# main.net
KiCad netlist of a schematic drawn in EAGLE
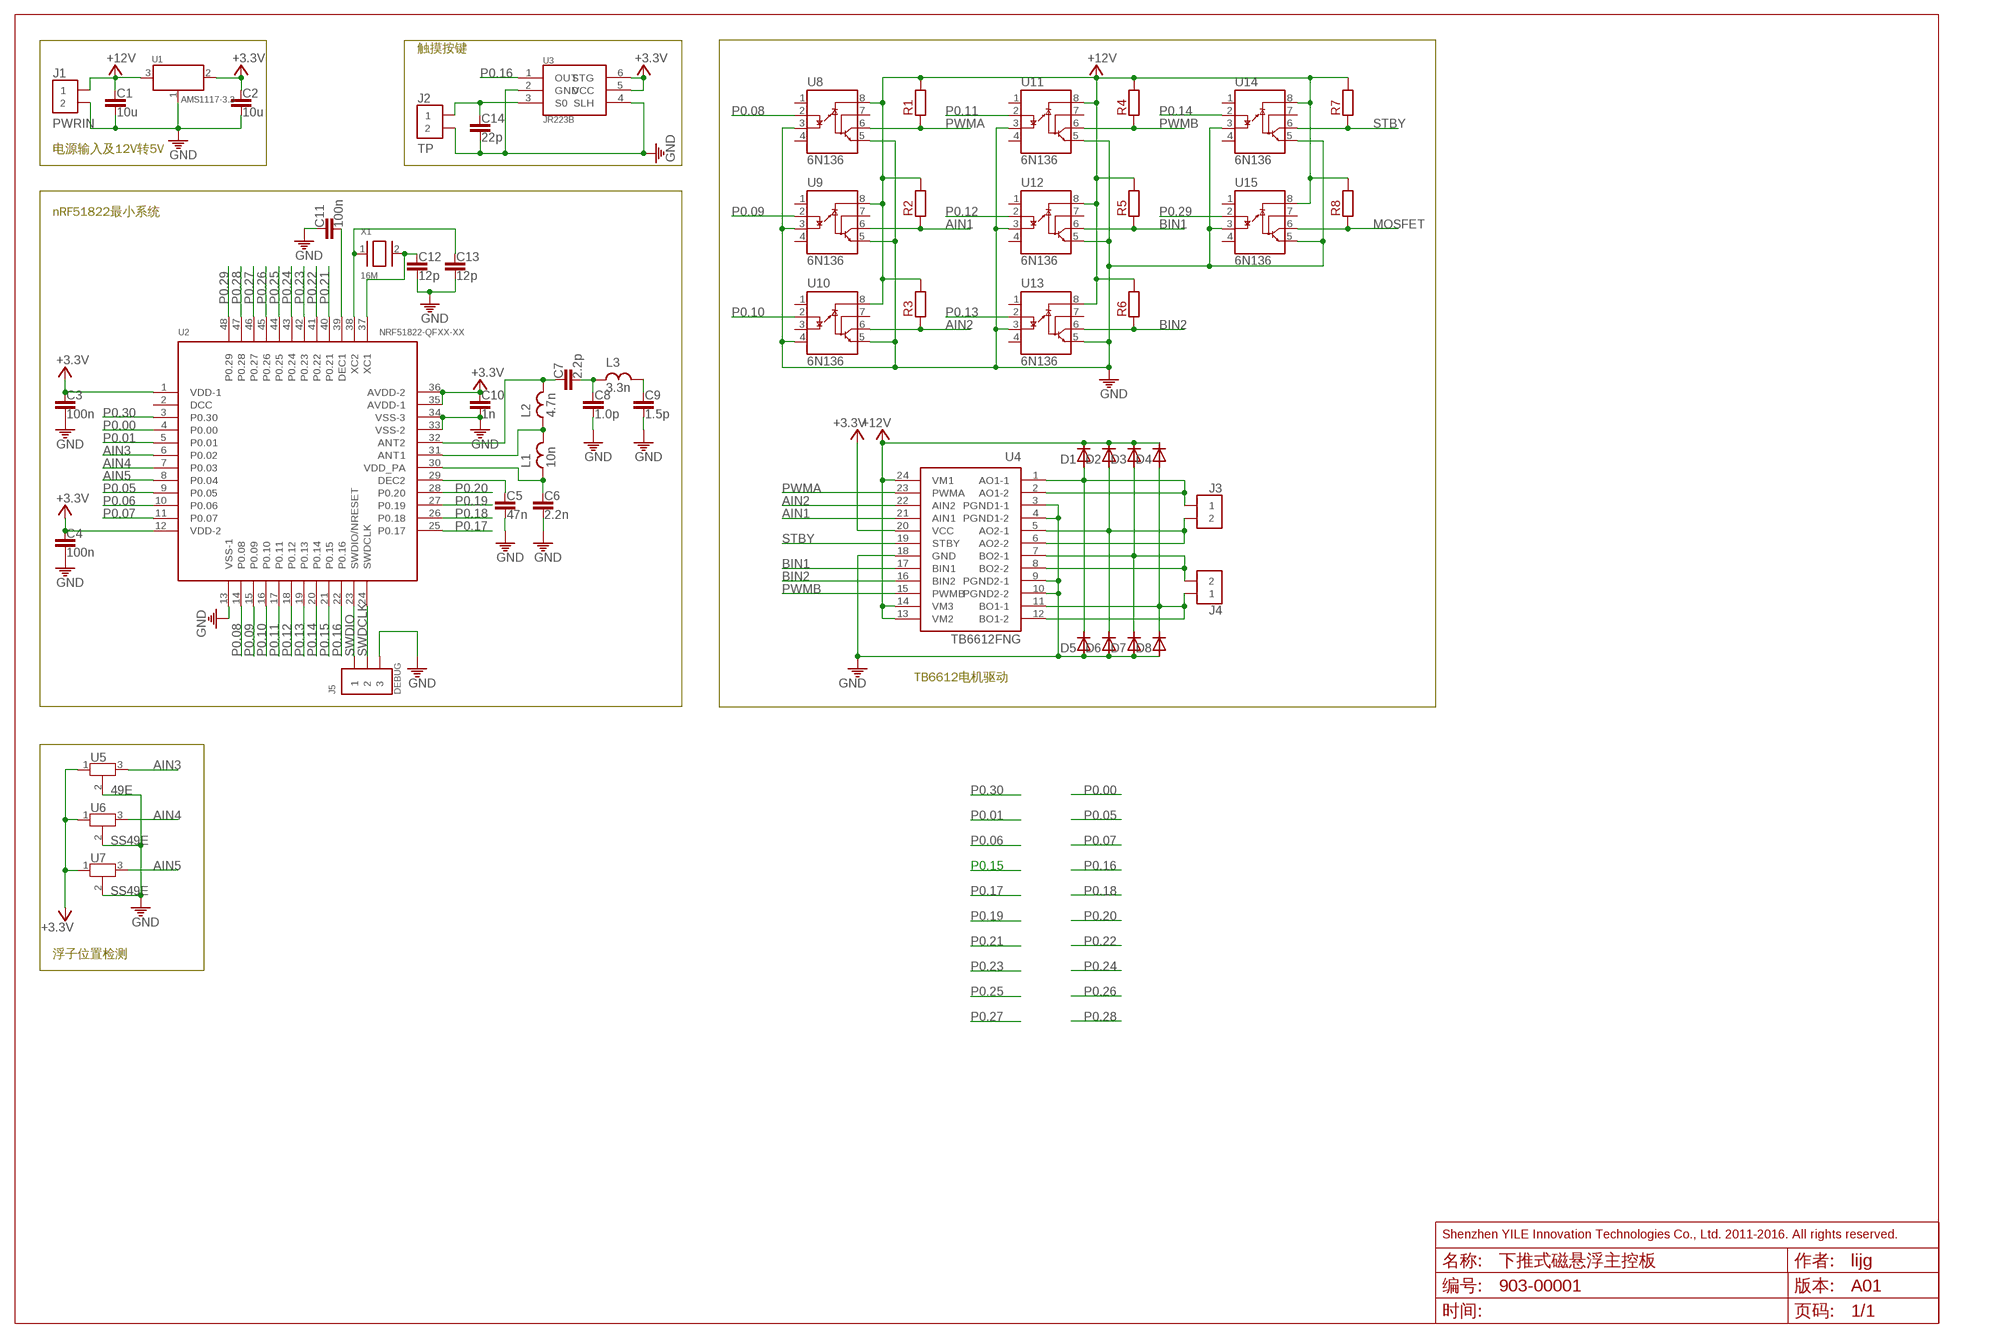
[diagram p0: schematic, sheet 1]

(export (version "E")
  (design (tool "Eeschema 10.0.6"))
  (components
    (comp (ref "C1")
      (value "10u")
      (footprint "eagle-import:0805")
      (libsource (lib "eagle-import") (part "C0805"))
    )
    (comp (ref "C2")
      (value "10u")
      (footprint "eagle-import:0805")
      (libsource (lib "eagle-import") (part "C0805"))
    )
    (comp (ref "C3")
      (value "100n")
      (footprint "eagle-import:0805")
      (libsource (lib "eagle-import") (part "C0805"))
    )
    (comp (ref "C4")
      (value "100n")
      (footprint "eagle-import:0805")
      (libsource (lib "eagle-import") (part "C0805"))
    )
    (comp (ref "C5")
      (value "47n")
      (footprint "eagle-import:0805")
      (libsource (lib "eagle-import") (part "C0805"))
    )
    (comp (ref "C6")
      (value "2.2n")
      (footprint "eagle-import:0805")
      (libsource (lib "eagle-import") (part "C0805"))
    )
    (comp (ref "C7")
      (value "2.2p")
      (footprint "eagle-import:0805")
      (libsource (lib "eagle-import") (part "C0805"))
    )
    (comp (ref "C8")
      (value "1.0p")
      (footprint "eagle-import:0805")
      (libsource (lib "eagle-import") (part "C0805"))
    )
    (comp (ref "C9")
      (value "1.5p")
      (footprint "eagle-import:0805")
      (libsource (lib "eagle-import") (part "C0805"))
    )
    (comp (ref "C10")
      (value "1n")
      (footprint "eagle-import:0805")
      (libsource (lib "eagle-import") (part "C0805"))
    )
    (comp (ref "C11")
      (value "100n")
      (footprint "eagle-import:0805")
      (libsource (lib "eagle-import") (part "C0805"))
    )
    (comp (ref "C12")
      (value "12p")
      (footprint "eagle-import:0805")
      (libsource (lib "eagle-import") (part "C0805"))
    )
    (comp (ref "C13")
      (value "12p")
      (footprint "eagle-import:0805")
      (libsource (lib "eagle-import") (part "C0805"))
    )
    (comp (ref "C14")
      (value "22p")
      (footprint "eagle-import:0805")
      (libsource (lib "eagle-import") (part "C0805"))
    )
    (comp (ref "D1")
      (value "D0805")
      (footprint "eagle-import:0805")
      (libsource (lib "eagle-import") (part "D0805"))
    )
    (comp (ref "D2")
      (value "D0805")
      (footprint "eagle-import:0805")
      (libsource (lib "eagle-import") (part "D0805"))
    )
    (comp (ref "D3")
      (value "D0805")
      (footprint "eagle-import:0805")
      (libsource (lib "eagle-import") (part "D0805"))
    )
    (comp (ref "D4")
      (value "D0805")
      (footprint "eagle-import:0805")
      (libsource (lib "eagle-import") (part "D0805"))
    )
    (comp (ref "D5")
      (value "D0805")
      (footprint "eagle-import:0805")
      (libsource (lib "eagle-import") (part "D0805"))
    )
    (comp (ref "D6")
      (value "D0805")
      (footprint "eagle-import:0805")
      (libsource (lib "eagle-import") (part "D0805"))
    )
    (comp (ref "D7")
      (value "D0805")
      (footprint "eagle-import:0805")
      (libsource (lib "eagle-import") (part "D0805"))
    )
    (comp (ref "D8")
      (value "D0805")
      (footprint "eagle-import:0805")
      (libsource (lib "eagle-import") (part "D0805"))
    )
    (comp (ref "J1")
      (value "PWRIN")
      (footprint "eagle-import:SIP2-100")
      (libsource (lib "eagle-import") (part "CON2X12X1-DIP2-100"))
    )
    (comp (ref "J2")
      (value "TP")
      (footprint "eagle-import:SIP2-100")
      (libsource (lib "eagle-import") (part "CON2X12X1-DIP2-100"))
    )
    (comp (ref "J3")
      (value "CON2X12X1-DIP2-100")
      (footprint "eagle-import:SIP2-100")
      (libsource (lib "eagle-import") (part "CON2X12X1-DIP2-100"))
    )
    (comp (ref "J4")
      (value "CON2X12X1-DIP2-100")
      (footprint "eagle-import:SIP2-100")
      (libsource (lib "eagle-import") (part "CON2X12X1-DIP2-100"))
    )
    (comp (ref "J5")
      (value "DEBUG")
      (footprint "eagle-import:SIP3-100")
      (libsource (lib "eagle-import") (part "CON3X1"))
    )
    (comp (ref "L1")
      (value "10n")
      (footprint "eagle-import:0805")
      (libsource (lib "eagle-import") (part "L0805"))
    )
    (comp (ref "L2")
      (value "4.7n")
      (footprint "eagle-import:0805")
      (libsource (lib "eagle-import") (part "L0805"))
    )
    (comp (ref "L3")
      (value "3.3n")
      (footprint "eagle-import:0805")
      (libsource (lib "eagle-import") (part "L0805"))
    )
    (comp (ref "R1")
      (value "R0805")
      (footprint "eagle-import:0805")
      (libsource (lib "eagle-import") (part "R0805"))
    )
    (comp (ref "R2")
      (value "R0805")
      (footprint "eagle-import:0805")
      (libsource (lib "eagle-import") (part "R0805"))
    )
    (comp (ref "R3")
      (value "R0805")
      (footprint "eagle-import:0805")
      (libsource (lib "eagle-import") (part "R0805"))
    )
    (comp (ref "R4")
      (value "R0805")
      (footprint "eagle-import:0805")
      (libsource (lib "eagle-import") (part "R0805"))
    )
    (comp (ref "R5")
      (value "R0805")
      (footprint "eagle-import:0805")
      (libsource (lib "eagle-import") (part "R0805"))
    )
    (comp (ref "R6")
      (value "R0805")
      (footprint "eagle-import:0805")
      (libsource (lib "eagle-import") (part "R0805"))
    )
    (comp (ref "R7")
      (value "R0805")
      (footprint "eagle-import:0805")
      (libsource (lib "eagle-import") (part "R0805"))
    )
    (comp (ref "R8")
      (value "R0805")
      (footprint "eagle-import:0805")
      (libsource (lib "eagle-import") (part "R0805"))
    )
    (comp (ref "U1")
      (value "AMS1117-3.3")
      (footprint "eagle-import:SOT-223")
      (libsource (lib "eagle-import") (part "AMS1117"))
    )
    (comp (ref "U2")
      (value "NRF51822-QFXX-XX")
      (footprint "eagle-import:QFN48-6.0A-0.4A")
      (libsource (lib "eagle-import") (part "NRF51822-QFXX-XX"))
    )
    (comp (ref "U3")
      (value "JR223B")
      (footprint "eagle-import:SSOP6-P-118-0.6A")
      (libsource (lib "eagle-import") (part "JR223B"))
    )
    (comp (ref "U4")
      (value "TB6612FNG")
      (footprint "eagle-import:SSOP24-P-300-0.65A")
      (libsource (lib "eagle-import") (part "TB6612FNG"))
    )
    (comp (ref "U5")
      (value "49E")
      (footprint "eagle-import:AH3503")
      (libsource (lib "eagle-import") (part "AH3503"))
    )
    (comp (ref "U6")
      (value "SS49E")
      (footprint "eagle-import:AH3503")
      (libsource (lib "eagle-import") (part "AH3503"))
    )
    (comp (ref "U7")
      (value "SS49E")
      (footprint "eagle-import:AH3503")
      (libsource (lib "eagle-import") (part "AH3503"))
    )
    (comp (ref "U8")
      (value "6N136")
      (footprint "eagle-import:SOP8-900A-2.54A")
      (libsource (lib "eagle-import") (part "6N136"))
    )
    (comp (ref "U9")
      (value "6N136")
      (footprint "eagle-import:SOP8-900A-2.54A")
      (libsource (lib "eagle-import") (part "6N136"))
    )
    (comp (ref "U10")
      (value "6N136")
      (footprint "eagle-import:SOP8-900A-2.54A")
      (libsource (lib "eagle-import") (part "6N136"))
    )
    (comp (ref "U11")
      (value "6N136")
      (footprint "eagle-import:SOP8-900A-2.54A")
      (libsource (lib "eagle-import") (part "6N136"))
    )
    (comp (ref "U12")
      (value "6N136")
      (footprint "eagle-import:SOP8-900A-2.54A")
      (libsource (lib "eagle-import") (part "6N136"))
    )
    (comp (ref "U13")
      (value "6N136")
      (footprint "eagle-import:SOP8-900A-2.54A")
      (libsource (lib "eagle-import") (part "6N136"))
    )
    (comp (ref "U14")
      (value "6N136")
      (footprint "eagle-import:SOP8-900A-2.54A")
      (libsource (lib "eagle-import") (part "6N136"))
    )
    (comp (ref "U15")
      (value "6N136")
      (footprint "eagle-import:SOP8-900A-2.54A")
      (libsource (lib "eagle-import") (part "6N136"))
    )
    (comp (ref "X1")
      (value "16M")
      (footprint "eagle-import:S5032B")
      (libsource (lib "eagle-import") (part "S5032B"))
    )
  )
  (nets
    (net (code "1") (name "+3.3V") (class "Default")
      (node (ref "C10") (pin "1") (pinfunction "1_1") (pintype "bidirectional"))
      (node (ref "C2") (pin "1") (pinfunction "1_1") (pintype "bidirectional"))
      (node (ref "C3") (pin "1") (pinfunction "1_1") (pintype "bidirectional"))
      (node (ref "C4") (pin "1") (pinfunction "1_1") (pintype "bidirectional"))
      (node (ref "U1") (pin "2") (pinfunction "VOUT_2") (pintype "bidirectional"))
      (node (ref "U2") (pin "1") (pinfunction "VDD-1_1") (pintype "bidirectional"))
      (node (ref "U2") (pin "12") (pinfunction "VDD-2_12") (pintype "bidirectional"))
      (node (ref "U2") (pin "35") (pinfunction "AVDD-1_35") (pintype "bidirectional"))
      (node (ref "U2") (pin "36") (pinfunction "AVDD-2_36") (pintype "bidirectional"))
      (node (ref "U3") (pin "5") (pinfunction "VCC_5") (pintype "bidirectional"))
      (node (ref "U3") (pin "6") (pinfunction "STG_6") (pintype "bidirectional"))
      (node (ref "U4") (pin "20") (pinfunction "VCC_20") (pintype "bidirectional"))
      (node (ref "U5") (pin "1") (pinfunction "P$1_1") (pintype "bidirectional"))
      (node (ref "U6") (pin "1") (pinfunction "P$1_1") (pintype "bidirectional"))
      (node (ref "U7") (pin "1") (pinfunction "P$1_1") (pintype "bidirectional"))
    )
    (net (code "2") (name "+12V") (class "Default")
      (node (ref "C1") (pin "1") (pinfunction "1_1") (pintype "bidirectional"))
      (node (ref "D1") (pin "2") (pinfunction "P$2_2") (pintype "bidirectional"))
      (node (ref "D2") (pin "2") (pinfunction "P$2_2") (pintype "bidirectional"))
      (node (ref "D3") (pin "2") (pinfunction "P$2_2") (pintype "bidirectional"))
      (node (ref "D4") (pin "2") (pinfunction "P$2_2") (pintype "bidirectional"))
      (node (ref "J1") (pin "P$1") (pinfunction "1_P$1") (pintype "bidirectional"))
      (node (ref "R1") (pin "2") (pinfunction "2_2") (pintype "bidirectional"))
      (node (ref "R2") (pin "2") (pinfunction "2_2") (pintype "bidirectional"))
      (node (ref "R3") (pin "2") (pinfunction "2_2") (pintype "bidirectional"))
      (node (ref "R4") (pin "2") (pinfunction "2_2") (pintype "bidirectional"))
      (node (ref "R5") (pin "2") (pinfunction "2_2") (pintype "bidirectional"))
      (node (ref "R6") (pin "2") (pinfunction "2_2") (pintype "bidirectional"))
      (node (ref "R7") (pin "2") (pinfunction "2_2") (pintype "bidirectional"))
      (node (ref "R8") (pin "2") (pinfunction "2_2") (pintype "bidirectional"))
      (node (ref "U1") (pin "3") (pinfunction "VIN_3") (pintype "bidirectional"))
      (node (ref "U10") (pin "8") (pinfunction "VCC_8") (pintype "bidirectional"))
      (node (ref "U11") (pin "8") (pinfunction "VCC_8") (pintype "bidirectional"))
      (node (ref "U12") (pin "8") (pinfunction "VCC_8") (pintype "bidirectional"))
      (node (ref "U13") (pin "8") (pinfunction "VCC_8") (pintype "bidirectional"))
      (node (ref "U14") (pin "8") (pinfunction "VCC_8") (pintype "bidirectional"))
      (node (ref "U15") (pin "8") (pinfunction "VCC_8") (pintype "bidirectional"))
      (node (ref "U4") (pin "13") (pinfunction "VM2_13") (pintype "bidirectional"))
      (node (ref "U4") (pin "14") (pinfunction "VM3_14") (pintype "bidirectional"))
      (node (ref "U4") (pin "24") (pinfunction "VM1_24") (pintype "bidirectional"))
      (node (ref "U8") (pin "8") (pinfunction "VCC_8") (pintype "bidirectional"))
      (node (ref "U9") (pin "8") (pinfunction "VCC_8") (pintype "bidirectional"))
    )
    (net (code "3") (name "/AIN1") (class "Default")
      (node (ref "R2") (pin "1") (pinfunction "1_1") (pintype "bidirectional"))
      (node (ref "U4") (pin "21") (pinfunction "AIN1_21") (pintype "bidirectional"))
      (node (ref "U9") (pin "6") (pinfunction "VO_6") (pintype "bidirectional"))
    )
    (net (code "4") (name "/AIN2") (class "Default")
      (node (ref "R3") (pin "1") (pinfunction "1_1") (pintype "bidirectional"))
      (node (ref "U10") (pin "6") (pinfunction "VO_6") (pintype "bidirectional"))
      (node (ref "U4") (pin "22") (pinfunction "AIN2_22") (pintype "bidirectional"))
    )
    (net (code "5") (name "/AIN3") (class "Default")
      (node (ref "U2") (pin "6") (pinfunction "P0.02_6") (pintype "bidirectional"))
      (node (ref "U5") (pin "3") (pinfunction "P$3_3") (pintype "bidirectional"))
    )
    (net (code "6") (name "/AIN4") (class "Default")
      (node (ref "U2") (pin "7") (pinfunction "P0.03_7") (pintype "bidirectional"))
      (node (ref "U6") (pin "3") (pinfunction "P$3_3") (pintype "bidirectional"))
    )
    (net (code "7") (name "/AIN5") (class "Default")
      (node (ref "U2") (pin "8") (pinfunction "P0.04_8") (pintype "bidirectional"))
      (node (ref "U7") (pin "3") (pinfunction "P$3_3") (pintype "bidirectional"))
    )
    (net (code "8") (name "/BIN1") (class "Default")
      (node (ref "R5") (pin "1") (pinfunction "1_1") (pintype "bidirectional"))
      (node (ref "U12") (pin "6") (pinfunction "VO_6") (pintype "bidirectional"))
      (node (ref "U4") (pin "17") (pinfunction "BIN1_17") (pintype "bidirectional"))
    )
    (net (code "9") (name "/BIN2") (class "Default")
      (node (ref "R6") (pin "1") (pinfunction "1_1") (pintype "bidirectional"))
      (node (ref "U13") (pin "6") (pinfunction "VO_6") (pintype "bidirectional"))
      (node (ref "U4") (pin "16") (pinfunction "BIN2_16") (pintype "bidirectional"))
    )
    (net (code "10") (name "/MOSFET") (class "Default")
      (node (ref "R8") (pin "1") (pinfunction "1_1") (pintype "bidirectional"))
      (node (ref "U15") (pin "6") (pinfunction "VO_6") (pintype "bidirectional"))
    )
    (net (code "11") (name "/P0.00") (class "Default")
      (node (ref "U2") (pin "4") (pinfunction "P0.00_4") (pintype "bidirectional"))
    )
    (net (code "12") (name "/P0.01") (class "Default")
      (node (ref "U2") (pin "5") (pinfunction "P0.01_5") (pintype "bidirectional"))
    )
    (net (code "13") (name "/P0.05") (class "Default")
      (node (ref "U2") (pin "9") (pinfunction "P0.05_9") (pintype "bidirectional"))
    )
    (net (code "14") (name "/P0.06") (class "Default")
      (node (ref "U2") (pin "10") (pinfunction "P0.06_10") (pintype "bidirectional"))
    )
    (net (code "15") (name "/P0.07") (class "Default")
      (node (ref "U2") (pin "11") (pinfunction "P0.07_11") (pintype "bidirectional"))
    )
    (net (code "16") (name "/P0.08") (class "Default")
      (node (ref "U2") (pin "14") (pinfunction "P0.08_14") (pintype "bidirectional"))
      (node (ref "U8") (pin "2") (pinfunction "A_2") (pintype "bidirectional"))
    )
    (net (code "17") (name "/P0.09") (class "Default")
      (node (ref "U2") (pin "15") (pinfunction "P0.09_15") (pintype "bidirectional"))
      (node (ref "U9") (pin "2") (pinfunction "A_2") (pintype "bidirectional"))
    )
    (net (code "18") (name "/P0.10") (class "Default")
      (node (ref "U10") (pin "2") (pinfunction "A_2") (pintype "bidirectional"))
      (node (ref "U2") (pin "16") (pinfunction "P0.10_16") (pintype "bidirectional"))
    )
    (net (code "19") (name "/P0.11") (class "Default")
      (node (ref "U11") (pin "2") (pinfunction "A_2") (pintype "bidirectional"))
      (node (ref "U2") (pin "17") (pinfunction "P0.11_17") (pintype "bidirectional"))
    )
    (net (code "20") (name "/P0.12") (class "Default")
      (node (ref "U12") (pin "2") (pinfunction "A_2") (pintype "bidirectional"))
      (node (ref "U2") (pin "18") (pinfunction "P0.12_18") (pintype "bidirectional"))
    )
    (net (code "21") (name "/P0.13") (class "Default")
      (node (ref "U13") (pin "2") (pinfunction "A_2") (pintype "bidirectional"))
      (node (ref "U2") (pin "19") (pinfunction "P0.13_19") (pintype "bidirectional"))
    )
    (net (code "22") (name "/P0.14") (class "Default")
      (node (ref "U14") (pin "2") (pinfunction "A_2") (pintype "bidirectional"))
      (node (ref "U2") (pin "20") (pinfunction "P0.14_20") (pintype "bidirectional"))
    )
    (net (code "23") (name "/P0.15") (class "Default")
      (node (ref "U2") (pin "21") (pinfunction "P0.15_21") (pintype "bidirectional"))
    )
    (net (code "24") (name "/P0.16") (class "Default")
      (node (ref "U2") (pin "22") (pinfunction "P0.16_22") (pintype "bidirectional"))
      (node (ref "U3") (pin "1") (pinfunction "OUT_1") (pintype "bidirectional"))
    )
    (net (code "25") (name "/P0.17") (class "Default")
      (node (ref "U2") (pin "25") (pinfunction "P0.17_25") (pintype "bidirectional"))
    )
    (net (code "26") (name "/P0.18") (class "Default")
      (node (ref "U2") (pin "26") (pinfunction "P0.18_26") (pintype "bidirectional"))
    )
    (net (code "27") (name "/P0.19") (class "Default")
      (node (ref "U2") (pin "27") (pinfunction "P0.19_27") (pintype "bidirectional"))
    )
    (net (code "28") (name "/P0.20") (class "Default")
      (node (ref "U2") (pin "28") (pinfunction "P0.20_28") (pintype "bidirectional"))
    )
    (net (code "29") (name "/P0.21") (class "Default")
      (node (ref "U2") (pin "40") (pinfunction "P0.21_40") (pintype "bidirectional"))
    )
    (net (code "30") (name "/P0.22") (class "Default")
      (node (ref "U2") (pin "41") (pinfunction "P0.22_41") (pintype "bidirectional"))
    )
    (net (code "31") (name "/P0.23") (class "Default")
      (node (ref "U2") (pin "42") (pinfunction "P0.23_42") (pintype "bidirectional"))
    )
    (net (code "32") (name "/P0.24") (class "Default")
      (node (ref "U2") (pin "43") (pinfunction "P0.24_43") (pintype "bidirectional"))
    )
    (net (code "33") (name "/P0.25") (class "Default")
      (node (ref "U2") (pin "44") (pinfunction "P0.25_44") (pintype "bidirectional"))
    )
    (net (code "34") (name "/P0.26") (class "Default")
      (node (ref "U2") (pin "45") (pinfunction "P0.26_45") (pintype "bidirectional"))
    )
    (net (code "35") (name "/P0.27") (class "Default")
      (node (ref "U2") (pin "46") (pinfunction "P0.27_46") (pintype "bidirectional"))
    )
    (net (code "36") (name "/P0.28") (class "Default")
      (node (ref "U2") (pin "47") (pinfunction "P0.28_47") (pintype "bidirectional"))
    )
    (net (code "37") (name "/P0.29") (class "Default")
      (node (ref "U15") (pin "2") (pinfunction "A_2") (pintype "bidirectional"))
      (node (ref "U2") (pin "48") (pinfunction "P0.29_48") (pintype "bidirectional"))
    )
    (net (code "38") (name "/P0.30") (class "Default")
      (node (ref "U2") (pin "3") (pinfunction "P0.30_3") (pintype "bidirectional"))
    )
    (net (code "39") (name "/PWMA") (class "Default")
      (node (ref "R1") (pin "1") (pinfunction "1_1") (pintype "bidirectional"))
      (node (ref "U4") (pin "23") (pinfunction "PWMA_23") (pintype "bidirectional"))
      (node (ref "U8") (pin "6") (pinfunction "VO_6") (pintype "bidirectional"))
    )
    (net (code "40") (name "/PWMB") (class "Default")
      (node (ref "R4") (pin "1") (pinfunction "1_1") (pintype "bidirectional"))
      (node (ref "U11") (pin "6") (pinfunction "VO_6") (pintype "bidirectional"))
      (node (ref "U4") (pin "15") (pinfunction "PWMB_15") (pintype "bidirectional"))
    )
    (net (code "41") (name "/STBY") (class "Default")
      (node (ref "R7") (pin "1") (pinfunction "1_1") (pintype "bidirectional"))
      (node (ref "U14") (pin "6") (pinfunction "VO_6") (pintype "bidirectional"))
      (node (ref "U4") (pin "19") (pinfunction "STBY_19") (pintype "bidirectional"))
    )
    (net (code "42") (name "/SWDCLK") (class "Default")
      (node (ref "J5") (pin "P$2") (pinfunction "2_P$2") (pintype "bidirectional"))
      (node (ref "U2") (pin "24") (pinfunction "SWDCLK_24") (pintype "bidirectional"))
    )
    (net (code "43") (name "/SWDIO") (class "Default")
      (node (ref "J5") (pin "P$1") (pinfunction "1_P$1") (pintype "bidirectional"))
      (node (ref "U2") (pin "23") (pinfunction "SWDIO/NRESET_23") (pintype "bidirectional"))
    )
    (net (code "44") (name "GND") (class "Default")
      (node (ref "C1") (pin "2") (pinfunction "2_2") (pintype "bidirectional"))
      (node (ref "C10") (pin "2") (pinfunction "2_2") (pintype "bidirectional"))
      (node (ref "C11") (pin "1") (pinfunction "1_1") (pintype "bidirectional"))
      (node (ref "C12") (pin "2") (pinfunction "2_2") (pintype "bidirectional"))
      (node (ref "C13") (pin "2") (pinfunction "2_2") (pintype "bidirectional"))
      (node (ref "C14") (pin "2") (pinfunction "2_2") (pintype "bidirectional"))
      (node (ref "C2") (pin "2") (pinfunction "2_2") (pintype "bidirectional"))
      (node (ref "C3") (pin "2") (pinfunction "2_2") (pintype "bidirectional"))
      (node (ref "C4") (pin "2") (pinfunction "2_2") (pintype "bidirectional"))
      (node (ref "C5") (pin "2") (pinfunction "2_2") (pintype "bidirectional"))
      (node (ref "C6") (pin "2") (pinfunction "2_2") (pintype "bidirectional"))
      (node (ref "C8") (pin "2") (pinfunction "2_2") (pintype "bidirectional"))
      (node (ref "C9") (pin "2") (pinfunction "2_2") (pintype "bidirectional"))
      (node (ref "D5") (pin "1") (pinfunction "P$1_1") (pintype "bidirectional"))
      (node (ref "D6") (pin "1") (pinfunction "P$1_1") (pintype "bidirectional"))
      (node (ref "D7") (pin "1") (pinfunction "P$1_1") (pintype "bidirectional"))
      (node (ref "D8") (pin "1") (pinfunction "P$1_1") (pintype "bidirectional"))
      (node (ref "J1") (pin "P$2") (pinfunction "2_P$2") (pintype "bidirectional"))
      (node (ref "J2") (pin "P$2") (pinfunction "2_P$2") (pintype "bidirectional"))
      (node (ref "J5") (pin "P$3") (pinfunction "3_P$3") (pintype "bidirectional"))
      (node (ref "U1") (pin "1") (pinfunction "GND/ADJ_1") (pintype "bidirectional"))
      (node (ref "U10") (pin "4") (pinfunction "NC2_4") (pintype "bidirectional"))
      (node (ref "U10") (pin "5") (pinfunction "GND_5") (pintype "bidirectional"))
      (node (ref "U11") (pin "3") (pinfunction "C_3") (pintype "bidirectional"))
      (node (ref "U11") (pin "5") (pinfunction "GND_5") (pintype "bidirectional"))
      (node (ref "U12") (pin "3") (pinfunction "C_3") (pintype "bidirectional"))
      (node (ref "U12") (pin "5") (pinfunction "GND_5") (pintype "bidirectional"))
      (node (ref "U13") (pin "3") (pinfunction "C_3") (pintype "bidirectional"))
      (node (ref "U13") (pin "5") (pinfunction "GND_5") (pintype "bidirectional"))
      (node (ref "U14") (pin "3") (pinfunction "C_3") (pintype "bidirectional"))
      (node (ref "U14") (pin "5") (pinfunction "GND_5") (pintype "bidirectional"))
      (node (ref "U15") (pin "3") (pinfunction "C_3") (pintype "bidirectional"))
      (node (ref "U15") (pin "5") (pinfunction "GND_5") (pintype "bidirectional"))
      (node (ref "U2") (pin "13") (pinfunction "VSS-1_13") (pintype "bidirectional"))
      (node (ref "U2") (pin "33") (pinfunction "VSS-2_33") (pintype "bidirectional"))
      (node (ref "U2") (pin "34") (pinfunction "VSS-3_34") (pintype "bidirectional"))
      (node (ref "U3") (pin "2") (pinfunction "GND_2") (pintype "bidirectional"))
      (node (ref "U3") (pin "4") (pinfunction "SLH_4") (pintype "bidirectional"))
      (node (ref "U4") (pin "10") (pinfunction "PGND2-2_10") (pintype "bidirectional"))
      (node (ref "U4") (pin "18") (pinfunction "GND_18") (pintype "bidirectional"))
      (node (ref "U4") (pin "3") (pinfunction "PGND1-1_3") (pintype "bidirectional"))
      (node (ref "U4") (pin "4") (pinfunction "PGND1-2_4") (pintype "bidirectional"))
      (node (ref "U4") (pin "9") (pinfunction "PGND2-1_9") (pintype "bidirectional"))
      (node (ref "U5") (pin "2") (pinfunction "P$2_2") (pintype "bidirectional"))
      (node (ref "U6") (pin "2") (pinfunction "P$2_2") (pintype "bidirectional"))
      (node (ref "U7") (pin "2") (pinfunction "P$2_2") (pintype "bidirectional"))
      (node (ref "U8") (pin "3") (pinfunction "C_3") (pintype "bidirectional"))
      (node (ref "U8") (pin "5") (pinfunction "GND_5") (pintype "bidirectional"))
      (node (ref "U9") (pin "3") (pinfunction "C_3") (pintype "bidirectional"))
      (node (ref "U9") (pin "5") (pinfunction "GND_5") (pintype "bidirectional"))
    )
    (net (code "45") (name "Net-(C7-Pad2)") (class "Default")
      (node (ref "C7") (pin "2") (pinfunction "2_2") (pintype "bidirectional"))
      (node (ref "C8") (pin "1") (pinfunction "1_1") (pintype "bidirectional"))
      (node (ref "L3") (pin "1") (pinfunction "1_1") (pintype "bidirectional"))
    )
    (net (code "46") (name "Net-(C9-Pad1)") (class "Default")
      (node (ref "C9") (pin "1") (pinfunction "1_1") (pintype "bidirectional"))
      (node (ref "L3") (pin "2") (pinfunction "2_2") (pintype "bidirectional"))
    )
    (net (code "47") (name "Net-(D1-P$1)") (class "Default")
      (node (ref "D1") (pin "1") (pinfunction "P$1_1") (pintype "bidirectional"))
      (node (ref "D5") (pin "2") (pinfunction "P$2_2") (pintype "bidirectional"))
      (node (ref "J3") (pin "P$1") (pinfunction "1_P$1") (pintype "bidirectional"))
      (node (ref "U4") (pin "1") (pinfunction "AO1-1_1") (pintype "bidirectional"))
      (node (ref "U4") (pin "2") (pinfunction "AO1-2_2") (pintype "bidirectional"))
    )
    (net (code "48") (name "Net-(D2-P$1)") (class "Default")
      (node (ref "D2") (pin "1") (pinfunction "P$1_1") (pintype "bidirectional"))
      (node (ref "D6") (pin "2") (pinfunction "P$2_2") (pintype "bidirectional"))
      (node (ref "J3") (pin "P$2") (pinfunction "2_P$2") (pintype "bidirectional"))
      (node (ref "U4") (pin "5") (pinfunction "AO2-1_5") (pintype "bidirectional"))
      (node (ref "U4") (pin "6") (pinfunction "AO2-2_6") (pintype "bidirectional"))
    )
    (net (code "49") (name "Net-(D3-P$1)") (class "Default")
      (node (ref "D3") (pin "1") (pinfunction "P$1_1") (pintype "bidirectional"))
      (node (ref "D7") (pin "2") (pinfunction "P$2_2") (pintype "bidirectional"))
      (node (ref "J4") (pin "P$2") (pinfunction "2_P$2") (pintype "bidirectional"))
      (node (ref "U4") (pin "7") (pinfunction "BO2-1_7") (pintype "bidirectional"))
      (node (ref "U4") (pin "8") (pinfunction "BO2-2_8") (pintype "bidirectional"))
    )
    (net (code "50") (name "Net-(D4-P$1)") (class "Default")
      (node (ref "D4") (pin "1") (pinfunction "P$1_1") (pintype "bidirectional"))
      (node (ref "D8") (pin "2") (pinfunction "P$2_2") (pintype "bidirectional"))
      (node (ref "J4") (pin "P$1") (pinfunction "1_P$1") (pintype "bidirectional"))
      (node (ref "U4") (pin "11") (pinfunction "BO1-1_11") (pintype "bidirectional"))
      (node (ref "U4") (pin "12") (pinfunction "BO1-2_12") (pintype "bidirectional"))
    )
    (net (code "51") (name "Net-(J2-1)") (class "Default")
      (node (ref "C14") (pin "1") (pinfunction "1_1") (pintype "bidirectional"))
      (node (ref "J2") (pin "P$1") (pinfunction "1_P$1") (pintype "bidirectional"))
      (node (ref "U3") (pin "3") (pinfunction "S0_3") (pintype "bidirectional"))
    )
    (net (code "52") (name "Net-(U2-ANT1)") (class "Default")
      (node (ref "L1") (pin "2") (pinfunction "2_2") (pintype "bidirectional"))
      (node (ref "L2") (pin "1") (pinfunction "1_1") (pintype "bidirectional"))
      (node (ref "U2") (pin "31") (pinfunction "ANT1_31") (pintype "bidirectional"))
    )
    (net (code "53") (name "Net-(U2-ANT2)") (class "Default")
      (node (ref "C7") (pin "1") (pinfunction "1_1") (pintype "bidirectional"))
      (node (ref "L2") (pin "2") (pinfunction "2_2") (pintype "bidirectional"))
      (node (ref "U2") (pin "32") (pinfunction "ANT2_32") (pintype "bidirectional"))
    )
    (net (code "54") (name "Net-(U2-DEC1)") (class "Default")
      (node (ref "C11") (pin "2") (pinfunction "2_2") (pintype "bidirectional"))
      (node (ref "U2") (pin "39") (pinfunction "DEC1_39") (pintype "bidirectional"))
    )
    (net (code "55") (name "Net-(U2-DEC2)") (class "Default")
      (node (ref "C5") (pin "1") (pinfunction "1_1") (pintype "bidirectional"))
      (node (ref "U2") (pin "29") (pinfunction "DEC2_29") (pintype "bidirectional"))
    )
    (net (code "56") (name "Net-(U2-VDD_PA)") (class "Default")
      (node (ref "C6") (pin "1") (pinfunction "1_1") (pintype "bidirectional"))
      (node (ref "L1") (pin "1") (pinfunction "1_1") (pintype "bidirectional"))
      (node (ref "U2") (pin "30") (pinfunction "VDD_PA_30") (pintype "bidirectional"))
    )
    (net (code "57") (name "Net-(U2-XC1)") (class "Default")
      (node (ref "C12") (pin "1") (pinfunction "1_1") (pintype "bidirectional"))
      (node (ref "U2") (pin "37") (pinfunction "XC1_37") (pintype "bidirectional"))
      (node (ref "X1") (pin "2") (pinfunction "X2_2") (pintype "bidirectional"))
    )
    (net (code "58") (name "Net-(U2-XC2)") (class "Default")
      (node (ref "C13") (pin "1") (pinfunction "1_1") (pintype "bidirectional"))
      (node (ref "U2") (pin "38") (pinfunction "XC2_38") (pintype "bidirectional"))
      (node (ref "X1") (pin "1") (pinfunction "X1_1") (pintype "bidirectional"))
    )
    (net (code "59") (name "unconnected-(U2-DCC-Pad2)") (class "Default")
      (node (ref "U2") (pin "2") (pinfunction "DCC_2") (pintype "bidirectional"))
    )
    (net (code "60") (name "unconnected-(U8-NC1-Pad1)") (class "Default")
      (node (ref "U8") (pin "1") (pinfunction "NC1_1") (pintype "bidirectional"))
    )
    (net (code "61") (name "unconnected-(U8-NC2-Pad4)") (class "Default")
      (node (ref "U8") (pin "4") (pinfunction "NC2_4") (pintype "bidirectional"))
    )
    (net (code "62") (name "unconnected-(U8-VB-Pad7)") (class "Default")
      (node (ref "U8") (pin "7") (pinfunction "VB_7") (pintype "bidirectional"))
    )
    (net (code "63") (name "unconnected-(U9-NC1-Pad1)") (class "Default")
      (node (ref "U9") (pin "1") (pinfunction "NC1_1") (pintype "bidirectional"))
    )
    (net (code "64") (name "unconnected-(U9-NC2-Pad4)") (class "Default")
      (node (ref "U9") (pin "4") (pinfunction "NC2_4") (pintype "bidirectional"))
    )
    (net (code "65") (name "unconnected-(U9-VB-Pad7)") (class "Default")
      (node (ref "U9") (pin "7") (pinfunction "VB_7") (pintype "bidirectional"))
    )
    (net (code "66") (name "unconnected-(U10-C-Pad3)") (class "Default")
      (node (ref "U10") (pin "3") (pinfunction "C_3") (pintype "bidirectional"))
    )
    (net (code "67") (name "unconnected-(U10-NC1-Pad1)") (class "Default")
      (node (ref "U10") (pin "1") (pinfunction "NC1_1") (pintype "bidirectional"))
    )
    (net (code "68") (name "unconnected-(U10-VB-Pad7)") (class "Default")
      (node (ref "U10") (pin "7") (pinfunction "VB_7") (pintype "bidirectional"))
    )
    (net (code "69") (name "unconnected-(U11-NC1-Pad1)") (class "Default")
      (node (ref "U11") (pin "1") (pinfunction "NC1_1") (pintype "bidirectional"))
    )
    (net (code "70") (name "unconnected-(U11-NC2-Pad4)") (class "Default")
      (node (ref "U11") (pin "4") (pinfunction "NC2_4") (pintype "bidirectional"))
    )
    (net (code "71") (name "unconnected-(U11-VB-Pad7)") (class "Default")
      (node (ref "U11") (pin "7") (pinfunction "VB_7") (pintype "bidirectional"))
    )
    (net (code "72") (name "unconnected-(U12-NC1-Pad1)") (class "Default")
      (node (ref "U12") (pin "1") (pinfunction "NC1_1") (pintype "bidirectional"))
    )
    (net (code "73") (name "unconnected-(U12-NC2-Pad4)") (class "Default")
      (node (ref "U12") (pin "4") (pinfunction "NC2_4") (pintype "bidirectional"))
    )
    (net (code "74") (name "unconnected-(U12-VB-Pad7)") (class "Default")
      (node (ref "U12") (pin "7") (pinfunction "VB_7") (pintype "bidirectional"))
    )
    (net (code "75") (name "unconnected-(U13-NC1-Pad1)") (class "Default")
      (node (ref "U13") (pin "1") (pinfunction "NC1_1") (pintype "bidirectional"))
    )
    (net (code "76") (name "unconnected-(U13-NC2-Pad4)") (class "Default")
      (node (ref "U13") (pin "4") (pinfunction "NC2_4") (pintype "bidirectional"))
    )
    (net (code "77") (name "unconnected-(U13-VB-Pad7)") (class "Default")
      (node (ref "U13") (pin "7") (pinfunction "VB_7") (pintype "bidirectional"))
    )
    (net (code "78") (name "unconnected-(U14-NC1-Pad1)") (class "Default")
      (node (ref "U14") (pin "1") (pinfunction "NC1_1") (pintype "bidirectional"))
    )
    (net (code "79") (name "unconnected-(U14-NC2-Pad4)") (class "Default")
      (node (ref "U14") (pin "4") (pinfunction "NC2_4") (pintype "bidirectional"))
    )
    (net (code "80") (name "unconnected-(U14-VB-Pad7)") (class "Default")
      (node (ref "U14") (pin "7") (pinfunction "VB_7") (pintype "bidirectional"))
    )
    (net (code "81") (name "unconnected-(U15-NC1-Pad1)") (class "Default")
      (node (ref "U15") (pin "1") (pinfunction "NC1_1") (pintype "bidirectional"))
    )
    (net (code "82") (name "unconnected-(U15-NC2-Pad4)") (class "Default")
      (node (ref "U15") (pin "4") (pinfunction "NC2_4") (pintype "bidirectional"))
    )
    (net (code "83") (name "unconnected-(U15-VB-Pad7)") (class "Default")
      (node (ref "U15") (pin "7") (pinfunction "VB_7") (pintype "bidirectional"))
    )
  )
)
